# PGTNXEN_midi_inout.net
KiCad netlist of a schematic drawn in EAGLE
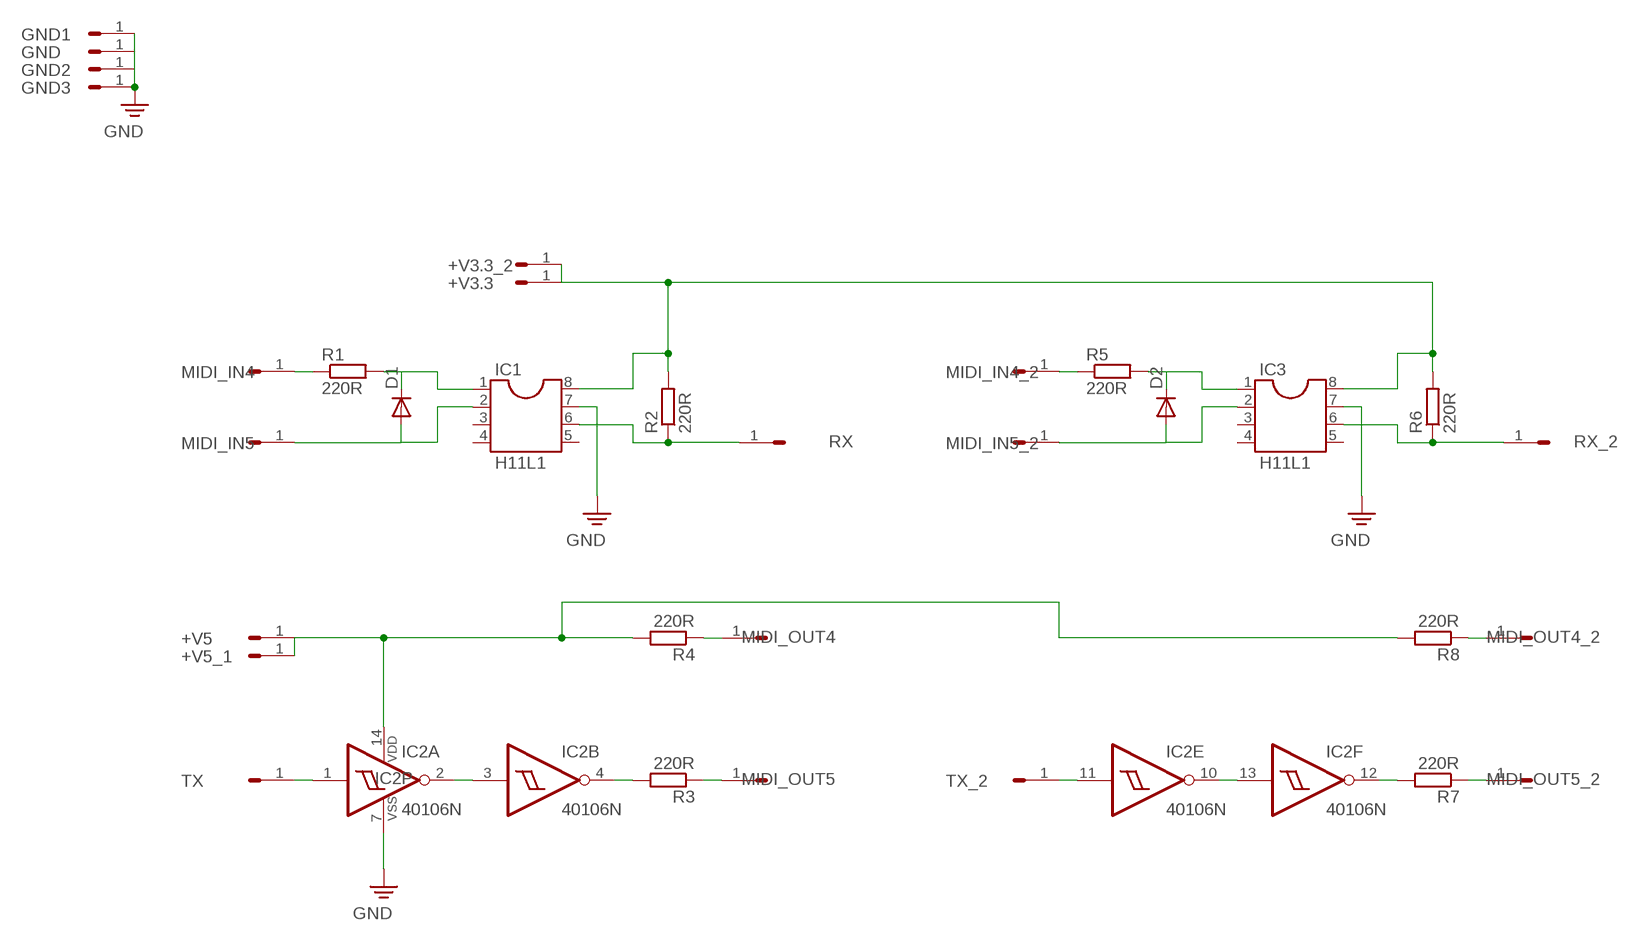
[diagram p0: schematic, sheet 1]

(export (version "E")
  (design (tool "Eeschema 10.0.6"))
  (components
    (comp (ref "+V3.3")
      (value "HEADER/MALE/01")
      (footprint "eagle-import:HEADER_MALE_01")
      (fields (field (name "SPICEPREFIX") "X"))
      (libsource (lib "eagle-import") (part "HEADER/MALE/01"))
    )
    (comp (ref "+V3.3_2")
      (value "HEADER/MALE/01")
      (footprint "eagle-import:HEADER_MALE_01")
      (fields (field (name "SPICEPREFIX") "X"))
      (libsource (lib "eagle-import") (part "HEADER/MALE/01"))
    )
    (comp (ref "+V5")
      (value "HEADER/MALE/01")
      (footprint "eagle-import:HEADER_MALE_01")
      (fields (field (name "SPICEPREFIX") "X"))
      (libsource (lib "eagle-import") (part "HEADER/MALE/01"))
    )
    (comp (ref "+V5_1")
      (value "HEADER/MALE/01")
      (footprint "eagle-import:HEADER_MALE_01")
      (fields (field (name "SPICEPREFIX") "X"))
      (libsource (lib "eagle-import") (part "HEADER/MALE/01"))
    )
    (comp (ref "D1")
      (value "1N4148DO35-7")
      (footprint "eagle-import:DO35-7")
      (libsource (lib "eagle-import") (part "1N4148DO35-7"))
    )
    (comp (ref "D2")
      (value "1N4148DO35-7")
      (footprint "eagle-import:DO35-7")
      (libsource (lib "eagle-import") (part "1N4148DO35-7"))
    )
    (comp (ref "GND")
      (value "HEADER/MALE/01")
      (footprint "eagle-import:HEADER_MALE_01")
      (fields (field (name "SPICEPREFIX") "X"))
      (libsource (lib "eagle-import") (part "HEADER/MALE/01"))
    )
    (comp (ref "GND1")
      (value "HEADER/MALE/01")
      (footprint "eagle-import:HEADER_MALE_01")
      (fields (field (name "SPICEPREFIX") "X"))
      (libsource (lib "eagle-import") (part "HEADER/MALE/01"))
    )
    (comp (ref "GND2")
      (value "HEADER/MALE/01")
      (footprint "eagle-import:HEADER_MALE_01")
      (fields (field (name "SPICEPREFIX") "X"))
      (libsource (lib "eagle-import") (part "HEADER/MALE/01"))
    )
    (comp (ref "GND3")
      (value "HEADER/MALE/01")
      (footprint "eagle-import:HEADER_MALE_01")
      (fields (field (name "SPICEPREFIX") "X"))
      (libsource (lib "eagle-import") (part "HEADER/MALE/01"))
    )
    (comp (ref "IC1")
      (value "H11L1")
      (footprint "eagle-import:DIL08")
      (libsource (lib "eagle-import") (part "DIL8"))
    )
    (comp (ref "IC2")
      (value "40106N")
      (footprint "eagle-import:DIL14")
      (libsource (lib "eagle-import") (part "40106N"))
    )
    (comp (ref "IC3")
      (value "H11L1")
      (footprint "eagle-import:DIL08")
      (libsource (lib "eagle-import") (part "DIL8"))
    )
    (comp (ref "MIDI_IN4")
      (value "HEADER/MALE/01")
      (footprint "eagle-import:HEADER_MALE_01")
      (fields (field (name "SPICEPREFIX") "X"))
      (libsource (lib "eagle-import") (part "HEADER/MALE/01"))
    )
    (comp (ref "MIDI_IN4_2")
      (value "HEADER/MALE/01")
      (footprint "eagle-import:HEADER_MALE_01")
      (fields (field (name "SPICEPREFIX") "X"))
      (libsource (lib "eagle-import") (part "HEADER/MALE/01"))
    )
    (comp (ref "MIDI_IN5")
      (value "HEADER/MALE/01")
      (footprint "eagle-import:HEADER_MALE_01")
      (fields (field (name "SPICEPREFIX") "X"))
      (libsource (lib "eagle-import") (part "HEADER/MALE/01"))
    )
    (comp (ref "MIDI_IN5_2")
      (value "HEADER/MALE/01")
      (footprint "eagle-import:HEADER_MALE_01")
      (fields (field (name "SPICEPREFIX") "X"))
      (libsource (lib "eagle-import") (part "HEADER/MALE/01"))
    )
    (comp (ref "MIDI_OUT4")
      (value "HEADER/MALE/01")
      (footprint "eagle-import:HEADER_MALE_01")
      (fields (field (name "SPICEPREFIX") "X"))
      (libsource (lib "eagle-import") (part "HEADER/MALE/01"))
    )
    (comp (ref "MIDI_OUT4_2")
      (value "HEADER/MALE/01")
      (footprint "eagle-import:HEADER_MALE_01")
      (fields (field (name "SPICEPREFIX") "X"))
      (libsource (lib "eagle-import") (part "HEADER/MALE/01"))
    )
    (comp (ref "MIDI_OUT5")
      (value "HEADER/MALE/01")
      (footprint "eagle-import:HEADER_MALE_01")
      (fields (field (name "SPICEPREFIX") "X"))
      (libsource (lib "eagle-import") (part "HEADER/MALE/01"))
    )
    (comp (ref "MIDI_OUT5_2")
      (value "HEADER/MALE/01")
      (footprint "eagle-import:HEADER_MALE_01")
      (fields (field (name "SPICEPREFIX") "X"))
      (libsource (lib "eagle-import") (part "HEADER/MALE/01"))
    )
    (comp (ref "R1")
      (value "220R")
      (footprint "eagle-import:RESISTOR_7.5")
      (libsource (lib "eagle-import") (part "RESISTORRESISTOR/UPRIGHT/7.5"))
    )
    (comp (ref "R2")
      (value "220R")
      (footprint "eagle-import:RESISTOR_7.5")
      (libsource (lib "eagle-import") (part "RESISTORRESISTOR/UPRIGHT/7.5"))
    )
    (comp (ref "R3")
      (value "220R")
      (footprint "eagle-import:RESISTOR_7.5")
      (libsource (lib "eagle-import") (part "RESISTORRESISTOR/UPRIGHT/7.5"))
    )
    (comp (ref "R4")
      (value "220R")
      (footprint "eagle-import:RESISTOR_7.5")
      (libsource (lib "eagle-import") (part "RESISTORRESISTOR/UPRIGHT/7.5"))
    )
    (comp (ref "R5")
      (value "220R")
      (footprint "eagle-import:RESISTOR_7.5")
      (libsource (lib "eagle-import") (part "RESISTORRESISTOR/UPRIGHT/7.5"))
    )
    (comp (ref "R6")
      (value "220R")
      (footprint "eagle-import:RESISTOR_7.5")
      (libsource (lib "eagle-import") (part "RESISTORRESISTOR/UPRIGHT/7.5"))
    )
    (comp (ref "R7")
      (value "220R")
      (footprint "eagle-import:RESISTOR_7.5")
      (libsource (lib "eagle-import") (part "RESISTORRESISTOR/UPRIGHT/7.5"))
    )
    (comp (ref "R8")
      (value "220R")
      (footprint "eagle-import:RESISTOR_7.5")
      (libsource (lib "eagle-import") (part "RESISTORRESISTOR/UPRIGHT/7.5"))
    )
    (comp (ref "RX")
      (value "HEADER/MALE/01")
      (footprint "eagle-import:HEADER_MALE_01")
      (fields (field (name "SPICEPREFIX") "X"))
      (libsource (lib "eagle-import") (part "HEADER/MALE/01"))
    )
    (comp (ref "RX_2")
      (value "HEADER/MALE/01")
      (footprint "eagle-import:HEADER_MALE_01")
      (fields (field (name "SPICEPREFIX") "X"))
      (libsource (lib "eagle-import") (part "HEADER/MALE/01"))
    )
    (comp (ref "TX")
      (value "HEADER/MALE/01")
      (footprint "eagle-import:HEADER_MALE_01")
      (fields (field (name "SPICEPREFIX") "X"))
      (libsource (lib "eagle-import") (part "HEADER/MALE/01"))
    )
    (comp (ref "TX_2")
      (value "HEADER/MALE/01")
      (footprint "eagle-import:HEADER_MALE_01")
      (fields (field (name "SPICEPREFIX") "X"))
      (libsource (lib "eagle-import") (part "HEADER/MALE/01"))
    )
  )
  (nets
    (net (code "1") (name "GND") (class "Default")
      (node (ref "GND") (pin "1") (pinfunction "3_1") (pintype "passive"))
      (node (ref "GND1") (pin "1") (pinfunction "3_1") (pintype "passive"))
      (node (ref "GND2") (pin "1") (pinfunction "3_1") (pintype "passive"))
      (node (ref "GND3") (pin "1") (pinfunction "3_1") (pintype "passive"))
      (node (ref "IC1") (pin "7") (pinfunction "7_7") (pintype "passive"))
      (node (ref "IC2") (pin "7") (pinfunction "VSS_7") (pintype "power_in"))
      (node (ref "IC3") (pin "7") (pinfunction "7_7") (pintype "passive"))
    )
    (net (code "2") (name "Net-(+V3.3-3)") (class "Default")
      (node (ref "+V3.3") (pin "1") (pinfunction "3_1") (pintype "passive"))
      (node (ref "+V3.3_2") (pin "1") (pinfunction "3_1") (pintype "passive"))
      (node (ref "IC1") (pin "8") (pinfunction "8_8") (pintype "passive"))
      (node (ref "IC3") (pin "8") (pinfunction "8_8") (pintype "passive"))
      (node (ref "R2") (pin "2") (pinfunction "2_2") (pintype "passive"))
      (node (ref "R6") (pin "2") (pinfunction "2_2") (pintype "passive"))
    )
    (net (code "3") (name "Net-(+V5-3)") (class "Default")
      (node (ref "+V5") (pin "1") (pinfunction "3_1") (pintype "passive"))
      (node (ref "+V5_1") (pin "1") (pinfunction "3_1") (pintype "passive"))
      (node (ref "IC2") (pin "14") (pinfunction "VDD_14") (pintype "power_in"))
      (node (ref "R4") (pin "2") (pinfunction "2_2") (pintype "passive"))
      (node (ref "R8") (pin "2") (pinfunction "2_2") (pintype "passive"))
    )
    (net (code "4") (name "Net-(D1-PadC)") (class "Default")
      (node (ref "D1") (pin "C") (pinfunction "C_C") (pintype "passive"))
      (node (ref "IC1") (pin "1") (pinfunction "1_1") (pintype "passive"))
      (node (ref "R1") (pin "2") (pinfunction "2_2") (pintype "passive"))
    )
    (net (code "5") (name "Net-(D2-PadC)") (class "Default")
      (node (ref "D2") (pin "C") (pinfunction "C_C") (pintype "passive"))
      (node (ref "IC3") (pin "1") (pinfunction "1_1") (pintype "passive"))
      (node (ref "R5") (pin "2") (pinfunction "2_2") (pintype "passive"))
    )
    (net (code "6") (name "Net-(IC2A-I)") (class "Default")
      (node (ref "IC2") (pin "1") (pinfunction "I_1") (pintype "input"))
      (node (ref "TX") (pin "1") (pinfunction "3_1") (pintype "passive"))
    )
    (net (code "7") (name "Net-(IC2A-O)") (class "Default")
      (node (ref "IC2") (pin "2") (pinfunction "O_2") (pintype "output"))
      (node (ref "IC2") (pin "3") (pinfunction "I_3") (pintype "input"))
    )
    (net (code "8") (name "Net-(IC2B-O)") (class "Default")
      (node (ref "IC2") (pin "4") (pinfunction "O_4") (pintype "output"))
      (node (ref "R3") (pin "2") (pinfunction "2_2") (pintype "passive"))
    )
    (net (code "9") (name "Net-(IC2E-I)") (class "Default")
      (node (ref "IC2") (pin "11") (pinfunction "I_11") (pintype "input"))
      (node (ref "TX_2") (pin "1") (pinfunction "3_1") (pintype "passive"))
    )
    (net (code "10") (name "Net-(IC2E-O)") (class "Default")
      (node (ref "IC2") (pin "10") (pinfunction "O_10") (pintype "output"))
      (node (ref "IC2") (pin "13") (pinfunction "I_13") (pintype "input"))
    )
    (net (code "11") (name "Net-(IC2F-O)") (class "Default")
      (node (ref "IC2") (pin "12") (pinfunction "O_12") (pintype "output"))
      (node (ref "R7") (pin "2") (pinfunction "2_2") (pintype "passive"))
    )
    (net (code "12") (name "Net-(MIDI_IN4-3)") (class "Default")
      (node (ref "MIDI_IN4") (pin "1") (pinfunction "3_1") (pintype "passive"))
      (node (ref "R1") (pin "1") (pinfunction "1_1") (pintype "passive"))
    )
    (net (code "13") (name "Net-(MIDI_IN4_2-3)") (class "Default")
      (node (ref "MIDI_IN4_2") (pin "1") (pinfunction "3_1") (pintype "passive"))
      (node (ref "R5") (pin "1") (pinfunction "1_1") (pintype "passive"))
    )
    (net (code "14") (name "Net-(MIDI_IN5-3)") (class "Default")
      (node (ref "D1") (pin "A") (pinfunction "A_A") (pintype "passive"))
      (node (ref "IC1") (pin "2") (pinfunction "2_2") (pintype "passive"))
      (node (ref "MIDI_IN5") (pin "1") (pinfunction "3_1") (pintype "passive"))
    )
    (net (code "15") (name "Net-(MIDI_IN5_2-3)") (class "Default")
      (node (ref "D2") (pin "A") (pinfunction "A_A") (pintype "passive"))
      (node (ref "IC3") (pin "2") (pinfunction "2_2") (pintype "passive"))
      (node (ref "MIDI_IN5_2") (pin "1") (pinfunction "3_1") (pintype "passive"))
    )
    (net (code "16") (name "Net-(MIDI_OUT4-3)") (class "Default")
      (node (ref "MIDI_OUT4") (pin "1") (pinfunction "3_1") (pintype "passive"))
      (node (ref "R4") (pin "1") (pinfunction "1_1") (pintype "passive"))
    )
    (net (code "17") (name "Net-(MIDI_OUT4_2-3)") (class "Default")
      (node (ref "MIDI_OUT4_2") (pin "1") (pinfunction "3_1") (pintype "passive"))
      (node (ref "R8") (pin "1") (pinfunction "1_1") (pintype "passive"))
    )
    (net (code "18") (name "Net-(MIDI_OUT5-3)") (class "Default")
      (node (ref "MIDI_OUT5") (pin "1") (pinfunction "3_1") (pintype "passive"))
      (node (ref "R3") (pin "1") (pinfunction "1_1") (pintype "passive"))
    )
    (net (code "19") (name "Net-(MIDI_OUT5_2-3)") (class "Default")
      (node (ref "MIDI_OUT5_2") (pin "1") (pinfunction "3_1") (pintype "passive"))
      (node (ref "R7") (pin "1") (pinfunction "1_1") (pintype "passive"))
    )
    (net (code "20") (name "Net-(RX-3)") (class "Default")
      (node (ref "IC1") (pin "6") (pinfunction "6_6") (pintype "passive"))
      (node (ref "R2") (pin "1") (pinfunction "1_1") (pintype "passive"))
      (node (ref "RX") (pin "1") (pinfunction "3_1") (pintype "passive"))
    )
    (net (code "21") (name "Net-(RX_2-3)") (class "Default")
      (node (ref "IC3") (pin "6") (pinfunction "6_6") (pintype "passive"))
      (node (ref "R6") (pin "1") (pinfunction "1_1") (pintype "passive"))
      (node (ref "RX_2") (pin "1") (pinfunction "3_1") (pintype "passive"))
    )
    (net (code "22") (name "unconnected-(IC1-Pad3)") (class "Default")
      (node (ref "IC1") (pin "3") (pinfunction "3_3") (pintype "passive"))
    )
    (net (code "23") (name "unconnected-(IC1-Pad4)") (class "Default")
      (node (ref "IC1") (pin "4") (pinfunction "4_4") (pintype "passive"))
    )
    (net (code "24") (name "unconnected-(IC1-Pad5)") (class "Default")
      (node (ref "IC1") (pin "5") (pinfunction "5_5") (pintype "passive"))
    )
    (net (code "25") (name "unconnected-(IC3-Pad3)") (class "Default")
      (node (ref "IC3") (pin "3") (pinfunction "3_3") (pintype "passive"))
    )
    (net (code "26") (name "unconnected-(IC3-Pad4)") (class "Default")
      (node (ref "IC3") (pin "4") (pinfunction "4_4") (pintype "passive"))
    )
    (net (code "27") (name "unconnected-(IC3-Pad5)") (class "Default")
      (node (ref "IC3") (pin "5") (pinfunction "5_5") (pintype "passive"))
    )
  )
)
